# AmplifierOutput.net
KiCad netlist of a schematic drawn in Altium Designer
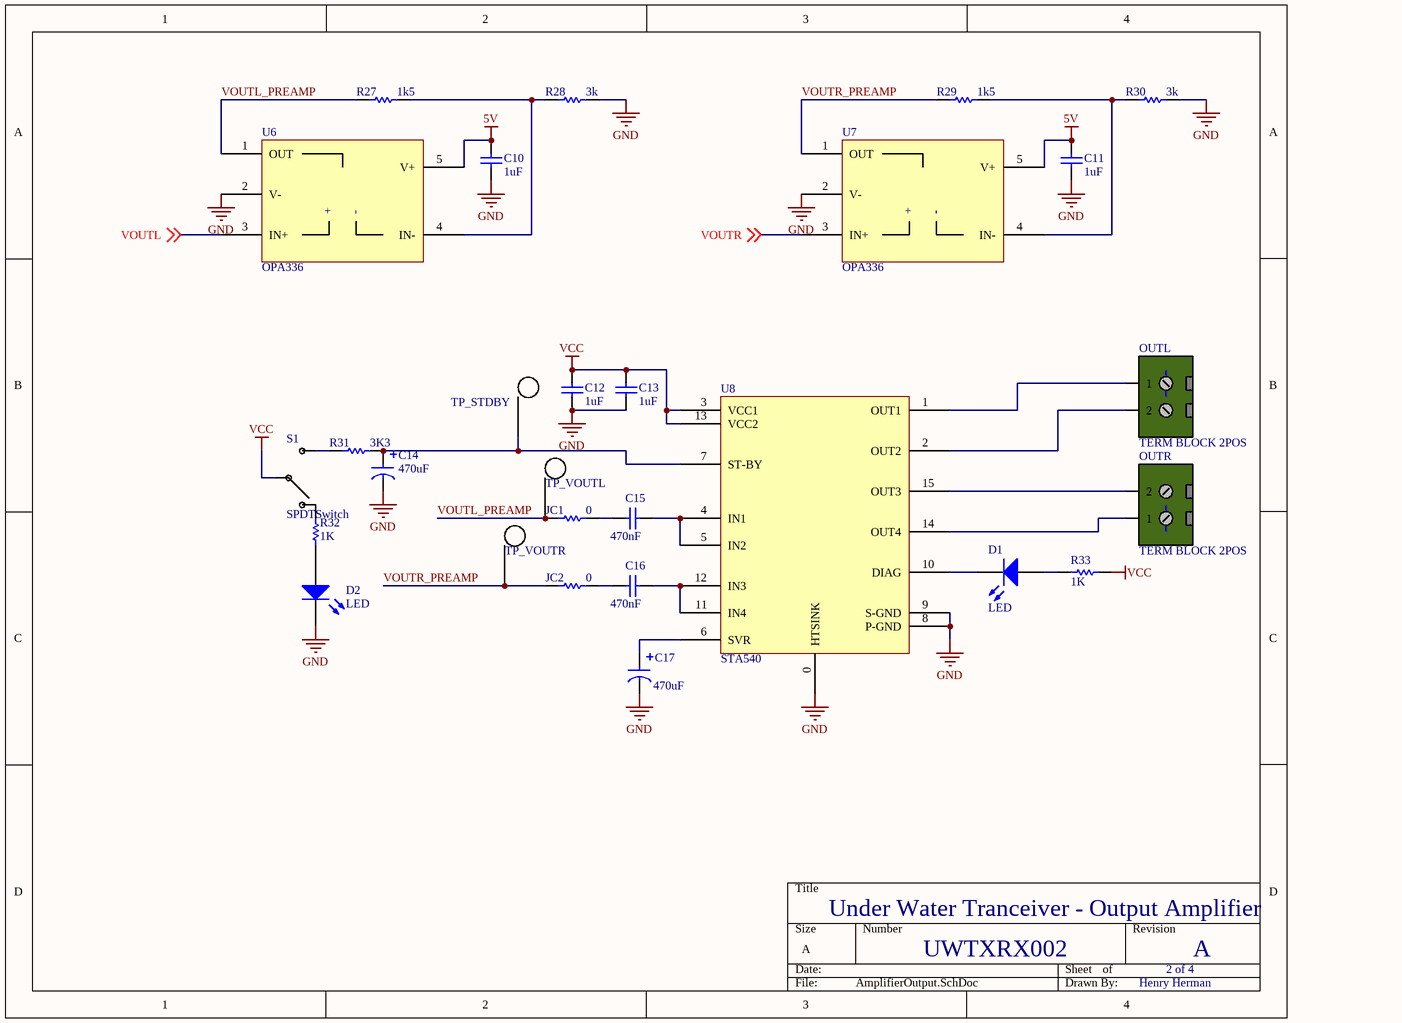
[diagram p0: AmplifierOutput.SchDoc]

(export (version "E")
  (design (tool "Eeschema 10.0.6"))
  (components
    (comp (ref "C10")
      (value "1uF")
      (footprint "SM/C_0805")
      (description "CAP")
      (libsource (lib "Henry1_20_2010") (part "CAP"))
    )
    (comp (ref "C11")
      (value "1uF")
      (footprint "SM/C_0805")
      (description "CAP")
      (libsource (lib "Henry1_20_2010") (part "CAP"))
    )
    (comp (ref "C12")
      (value "1uF")
      (footprint "SM/C_0805")
      (description "CAP")
      (libsource (lib "Henry1_20_2010") (part "CAP"))
    )
    (comp (ref "C13")
      (value "1uF")
      (footprint "SM/C_0805")
      (description "CAP")
      (libsource (lib "Henry1_20_2010") (part "CAP"))
    )
    (comp (ref "C14")
      (value "470uF")
      (footprint "SM/CT_6032_12")
      (description "CAP")
      (fields (field (name "Comment") "CAP_POL"))
      (libsource (lib "Henry1_20_2010") (part "CAP_POL"))
    )
    (comp (ref "C15")
      (value "470nF")
      (footprint "SM/C_0805")
      (description "CAP")
      (libsource (lib "Henry1_20_2010") (part "CAP"))
    )
    (comp (ref "C16")
      (value "470nF")
      (footprint "SM/C_0805")
      (description "CAP")
      (libsource (lib "Henry1_20_2010") (part "CAP"))
    )
    (comp (ref "C17")
      (value "470uF")
      (footprint "SM/CT_6032_12")
      (description "CAP")
      (fields (field (name "Comment") "CAP_POL"))
      (libsource (lib "Henry1_20_2010") (part "CAP_POL"))
    )
    (comp (ref "D1") (value "LED") (footprint "LED-0805") (libsource (lib "Henry1_20_2010") (part "LED")))
    (comp (ref "D2") (value "LED") (footprint "LED-0805") (libsource (lib "Henry1_20_2010") (part "LED")))
    (comp (ref "JC1")
      (value "0")
      (footprint "SM/R_0805")
      (description "Resistor")
      (fields (field (name "Comment") "Res") (field (name "PUBLISHER") "Altium Limited"))
      (libsource (lib "Henry1_20_2010") (part "Res"))
    )
    (comp (ref "JC2")
      (value "0")
      (footprint "SM/R_0805")
      (description "Resistor")
      (fields (field (name "Comment") "Res") (field (name "PUBLISHER") "Altium Limited"))
      (libsource (lib "Henry1_20_2010") (part "Res"))
    )
    (comp (ref "OUTL")
      (value "TERM BLOCK 2POS")
      (footprint "Conn-ScrewTerminal-2pin-Phoenix")
      (libsource (lib "Henry1_20_2010") (part "2Pin-PhoenixTerminalBlock"))
    )
    (comp (ref "OUTR")
      (value "TERM BLOCK 2POS")
      (footprint "Conn-ScrewTerminal-2pin-Phoenix")
      (libsource (lib "") (part "2Pin-PhoenixTerminalBlock_1"))
    )
    (comp (ref "R27")
      (value "1k5")
      (footprint "SM/R_0805")
      (description "Resistor")
      (fields (field (name "Comment") "Res") (field (name "PUBLISHER") "Altium Limited"))
      (libsource (lib "Henry1_20_2010") (part "Res"))
    )
    (comp (ref "R28")
      (value "3k")
      (footprint "SM/R_0805")
      (description "Resistor")
      (fields (field (name "Comment") "Res") (field (name "PUBLISHER") "Altium Limited"))
      (libsource (lib "Henry1_20_2010") (part "Res"))
    )
    (comp (ref "R29")
      (value "1k5")
      (footprint "SM/R_0805")
      (description "Resistor")
      (fields (field (name "Comment") "Res") (field (name "PUBLISHER") "Altium Limited"))
      (libsource (lib "Henry1_20_2010") (part "Res"))
    )
    (comp (ref "R30")
      (value "3k")
      (footprint "SM/R_0805")
      (description "Resistor")
      (fields (field (name "Comment") "Res") (field (name "PUBLISHER") "Altium Limited"))
      (libsource (lib "Henry1_20_2010") (part "Res"))
    )
    (comp (ref "R31")
      (value "3K3")
      (footprint "SM/R_0805")
      (description "Resistor")
      (fields (field (name "Comment") "Res") (field (name "PUBLISHER") "Altium Limited"))
      (libsource (lib "Henry1_20_2010") (part "Res"))
    )
    (comp (ref "R32")
      (value "1K")
      (footprint "SM/R_0805")
      (description "Resistor")
      (fields (field (name "Comment") "Res") (field (name "PUBLISHER") "Altium Limited"))
      (libsource (lib "Henry1_20_2010") (part "Res"))
    )
    (comp (ref "R33")
      (value "1K")
      (footprint "SM/R_0805")
      (description "Resistor")
      (fields (field (name "Comment") "Res") (field (name "PUBLISHER") "Altium Limited"))
      (libsource (lib "Henry1_20_2010") (part "Res"))
    )
    (comp (ref "S1")
      (value "SPDTSwitch")
      (footprint "SPDTSwitch")
      (libsource (lib "Henry1_20_2010") (part "SPDTSwitch"))
    )
    (comp (ref "TP_STDBY")
      (value "TEST_PT")
      (footprint "TEST_PT_SMD")
      (libsource (lib "Henry1_20_2010") (part "TEST_PT"))
    )
    (comp (ref "TP_VOUTL")
      (value "TEST_PT")
      (footprint "TEST_PT_SMD")
      (libsource (lib "Henry1_20_2010") (part "TEST_PT"))
    )
    (comp (ref "TP_VOUTR")
      (value "TEST_PT")
      (footprint "TEST_PT_SMD")
      (libsource (lib "Henry1_20_2010") (part "TEST_PT"))
    )
    (comp (ref "U6")
      (value "OPA336")
      (footprint "SOT23-5 -TI")
      (libsource (lib "Henry1_20_2010") (part "OPA335"))
    )
    (comp (ref "U7")
      (value "OPA336")
      (footprint "SOT23-5 -TI")
      (libsource (lib "Henry1_20_2010") (part "OPA335"))
    )
    (comp (ref "U8")
      (value "STA540")
      (footprint "STA540_Multiwatt15")
      (libsource (lib "Henry1_20_2010") (part "STA540"))
    )
  )
  (nets
    (net (code "1") (name "/VOUTL_PREAMP") (class "Default")
      (node (ref "JC1") (pin "1") (pinfunction "1_1") (pintype "passive"))
      (node (ref "R27") (pin "1") (pinfunction "1_1") (pintype "passive"))
      (node (ref "TP_VOUTL") (pin "1") (pinfunction "TP?_1") (pintype "passive"))
      (node (ref "U6") (pin "1") (pinfunction "OUT_1") (pintype "passive"))
    )
    (net (code "2") (name "/VOUTR_PREAMP") (class "Default")
      (node (ref "JC2") (pin "1") (pinfunction "1_1") (pintype "passive"))
      (node (ref "R29") (pin "1") (pinfunction "1_1") (pintype "passive"))
      (node (ref "TP_VOUTR") (pin "1") (pinfunction "TP?_1") (pintype "passive"))
      (node (ref "U7") (pin "1") (pinfunction "OUT_1") (pintype "passive"))
    )
    (net (code "3") (name "5V") (class "Default")
      (node (ref "C10") (pin "1") (pinfunction "1_1") (pintype "passive"))
      (node (ref "C11") (pin "1") (pinfunction "1_1") (pintype "passive"))
      (node (ref "U6") (pin "5") (pinfunction "V+_5") (pintype "passive"))
      (node (ref "U7") (pin "5") (pinfunction "V+_5") (pintype "passive"))
    )
    (net (code "4") (name "GND") (class "Default")
      (node (ref "C10") (pin "2") (pinfunction "2_2") (pintype "passive"))
      (node (ref "C11") (pin "2") (pinfunction "2_2") (pintype "passive"))
      (node (ref "C12") (pin "1") (pinfunction "1_1") (pintype "passive"))
      (node (ref "C13") (pin "1") (pinfunction "1_1") (pintype "passive"))
      (node (ref "C14") (pin "2") (pinfunction "2_2") (pintype "passive"))
      (node (ref "C17") (pin "2") (pinfunction "2_2") (pintype "passive"))
      (node (ref "D2") (pin "2") (pinfunction "K_2") (pintype "passive"))
      (node (ref "R28") (pin "2") (pinfunction "2_2") (pintype "passive"))
      (node (ref "R30") (pin "2") (pinfunction "2_2") (pintype "passive"))
      (node (ref "U6") (pin "2") (pinfunction "V-_2") (pintype "passive"))
      (node (ref "U7") (pin "2") (pinfunction "V-_2") (pintype "passive"))
      (node (ref "U8") (pin "0") (pinfunction "HTSINK_0") (pintype "passive"))
      (node (ref "U8") (pin "8") (pinfunction "P-GND_8") (pintype "passive"))
      (node (ref "U8") (pin "9") (pinfunction "S-GND_9") (pintype "passive"))
    )
    (net (code "5") (name "Net-(C15-Pad1)") (class "Default")
      (node (ref "C15") (pin "1") (pinfunction "1_1") (pintype "passive"))
      (node (ref "JC1") (pin "2") (pinfunction "2_2") (pintype "passive"))
    )
    (net (code "6") (name "Net-(C16-Pad1)") (class "Default")
      (node (ref "C16") (pin "1") (pinfunction "1_1") (pintype "passive"))
      (node (ref "JC2") (pin "2") (pinfunction "2_2") (pintype "passive"))
    )
    (net (code "7") (name "Net-(D1-A)") (class "Default")
      (node (ref "D1") (pin "1") (pinfunction "A_1") (pintype "passive"))
      (node (ref "R33") (pin "2") (pinfunction "2_2") (pintype "passive"))
    )
    (net (code "8") (name "Net-(D1-K)") (class "Default")
      (node (ref "D1") (pin "2") (pinfunction "K_2") (pintype "passive"))
      (node (ref "U8") (pin "10") (pinfunction "DIAG_10") (pintype "passive"))
    )
    (net (code "9") (name "Net-(D2-A)") (class "Default")
      (node (ref "D2") (pin "1") (pinfunction "A_1") (pintype "passive"))
      (node (ref "R32") (pin "2") (pinfunction "2_2") (pintype "passive"))
    )
    (net (code "10") (name "Net-(S1-P1)") (class "Default")
      (node (ref "R32") (pin "1") (pinfunction "1_1") (pintype "passive"))
      (node (ref "S1") (pin "1") (pinfunction "P1_1") (pintype "passive"))
    )
    (net (code "11") (name "Net-(S1-P2)") (class "Default")
      (node (ref "R31") (pin "1") (pinfunction "1_1") (pintype "passive"))
      (node (ref "S1") (pin "3") (pinfunction "P2_3") (pintype "passive"))
    )
    (net (code "12") (name "Net-(TP_STDBY-TP?)") (class "Default")
      (node (ref "C14") (pin "1") (pinfunction "1_1") (pintype "passive"))
      (node (ref "R31") (pin "2") (pinfunction "2_2") (pintype "passive"))
      (node (ref "TP_STDBY") (pin "1") (pinfunction "TP?_1") (pintype "passive"))
      (node (ref "U8") (pin "7") (pinfunction "ST-BY_7") (pintype "passive"))
    )
    (net (code "13") (name "Net-(U6-IN-)") (class "Default")
      (node (ref "R27") (pin "2") (pinfunction "2_2") (pintype "passive"))
      (node (ref "R28") (pin "1") (pinfunction "1_1") (pintype "passive"))
      (node (ref "U6") (pin "4") (pinfunction "IN-_4") (pintype "passive"))
    )
    (net (code "14") (name "Net-(U7-IN-)") (class "Default")
      (node (ref "R29") (pin "2") (pinfunction "2_2") (pintype "passive"))
      (node (ref "R30") (pin "1") (pinfunction "1_1") (pintype "passive"))
      (node (ref "U7") (pin "4") (pinfunction "IN-_4") (pintype "passive"))
    )
    (net (code "15") (name "Net-(U8-IN1)") (class "Default")
      (node (ref "C15") (pin "2") (pinfunction "2_2") (pintype "passive"))
      (node (ref "U8") (pin "4") (pinfunction "IN1_4") (pintype "passive"))
      (node (ref "U8") (pin "5") (pinfunction "IN2_5") (pintype "passive"))
    )
    (net (code "16") (name "Net-(U8-IN3)") (class "Default")
      (node (ref "C16") (pin "2") (pinfunction "2_2") (pintype "passive"))
      (node (ref "U8") (pin "11") (pinfunction "IN4_11") (pintype "passive"))
      (node (ref "U8") (pin "12") (pinfunction "IN3_12") (pintype "passive"))
    )
    (net (code "17") (name "Net-(U8-OUT1)") (class "Default")
      (node (ref "OUTL") (pin "1") (pinfunction "1_1") (pintype "passive"))
      (node (ref "U8") (pin "1") (pinfunction "OUT1_1") (pintype "passive"))
    )
    (net (code "18") (name "Net-(U8-OUT2)") (class "Default")
      (node (ref "OUTL") (pin "2") (pinfunction "2_2") (pintype "passive"))
      (node (ref "U8") (pin "2") (pinfunction "OUT2_2") (pintype "passive"))
    )
    (net (code "19") (name "Net-(U8-OUT3)") (class "Default")
      (node (ref "OUTR") (pin "2") (pinfunction "2_2") (pintype "passive"))
      (node (ref "U8") (pin "15") (pinfunction "OUT3_15") (pintype "passive"))
    )
    (net (code "20") (name "Net-(U8-OUT4)") (class "Default")
      (node (ref "OUTR") (pin "1") (pinfunction "1_1") (pintype "passive"))
      (node (ref "U8") (pin "14") (pinfunction "OUT4_14") (pintype "passive"))
    )
    (net (code "21") (name "Net-(U8-SVR)") (class "Default")
      (node (ref "C17") (pin "1") (pinfunction "1_1") (pintype "passive"))
      (node (ref "U8") (pin "6") (pinfunction "SVR_6") (pintype "passive"))
    )
    (net (code "22") (name "VCC") (class "Default")
      (node (ref "C12") (pin "2") (pinfunction "2_2") (pintype "passive"))
      (node (ref "C13") (pin "2") (pinfunction "2_2") (pintype "passive"))
      (node (ref "R33") (pin "1") (pinfunction "1_1") (pintype "passive"))
      (node (ref "S1") (pin "2") (pinfunction "C_2") (pintype "passive"))
      (node (ref "U8") (pin "13") (pinfunction "VCC2_13") (pintype "passive"))
      (node (ref "U8") (pin "3") (pinfunction "VCC1_3") (pintype "passive"))
    )
    (net (code "23") (name "VOUTL") (class "Default")
      (node (ref "U6") (pin "3") (pinfunction "IN+_3") (pintype "passive"))
    )
    (net (code "24") (name "VOUTR") (class "Default")
      (node (ref "U7") (pin "3") (pinfunction "IN+_3") (pintype "passive"))
    )
  )
)
